# upper_final.net
KiCad netlist of a schematic drawn in EAGLE
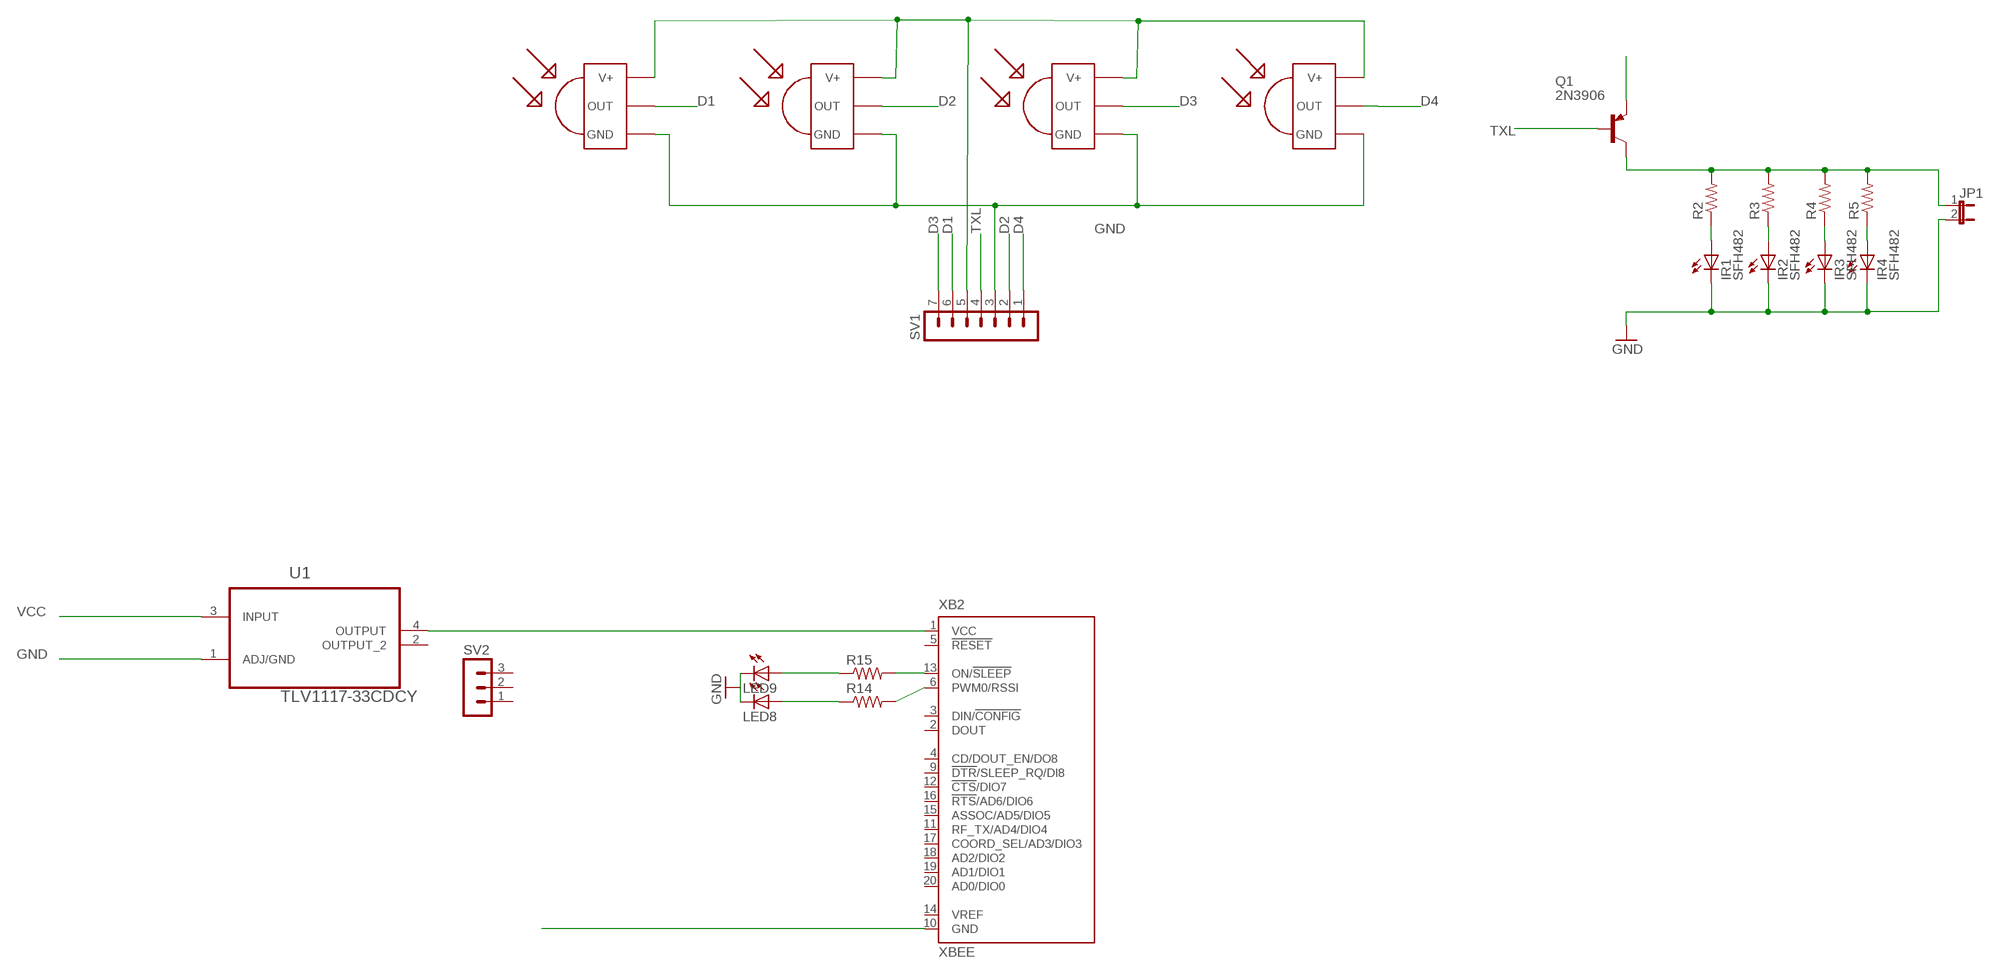
[diagram p0: schematic, sheet 1]

(export (version "E")
  (design (tool "Eeschema 10.0.6"))
  (components
    (comp (ref "IR1")
      (value "SFH482")
      (footprint "eagle-import:SFH482")
      (libsource (lib "eagle-import") (part "SFH482"))
    )
    (comp (ref "IR2")
      (value "SFH482")
      (footprint "eagle-import:SFH482")
      (libsource (lib "eagle-import") (part "SFH482"))
    )
    (comp (ref "IR3")
      (value "SFH482")
      (footprint "eagle-import:SFH482")
      (libsource (lib "eagle-import") (part "SFH482"))
    )
    (comp (ref "IR4")
      (value "SFH482")
      (footprint "eagle-import:SFH482")
      (libsource (lib "eagle-import") (part "SFH482"))
    )
    (comp (ref "JP1")
      (value "JP1E")
      (footprint "eagle-import:JP1")
      (libsource (lib "eagle-import") (part "JP1E"))
    )
    (comp (ref "LED8")
      (value "LED3MM")
      (footprint "eagle-import:LED3MM")
      (libsource (lib "eagle-import") (part "LED3MM"))
    )
    (comp (ref "LED9")
      (value "LED3MM")
      (footprint "eagle-import:LED3MM")
      (libsource (lib "eagle-import") (part "LED3MM"))
    )
    (comp (ref "Q1")
      (value "2N3906")
      (footprint "eagle-import:TO92")
      (libsource (lib "eagle-import") (part "2N3906"))
    )
    (comp (ref "R2")
      (value "R-US_0204/7")
      (footprint "eagle-import:0204_7")
      (libsource (lib "eagle-import") (part "resistor_R-US_0204/7"))
    )
    (comp (ref "R3")
      (value "R-US_0204/7")
      (footprint "eagle-import:0204_7")
      (libsource (lib "eagle-import") (part "resistor_R-US_0204/7"))
    )
    (comp (ref "R4")
      (value "R-US_0204/7")
      (footprint "eagle-import:0204_7")
      (libsource (lib "eagle-import") (part "resistor_R-US_0204/7"))
    )
    (comp (ref "R5")
      (value "R-US_0204/7")
      (footprint "eagle-import:0204_7")
      (libsource (lib "eagle-import") (part "resistor_R-US_0204/7"))
    )
    (comp (ref "R14")
      (value "R-US_0207/10")
      (footprint "eagle-import:0207_10")
      (libsource (lib "eagle-import") (part "R-US_0207/10"))
    )
    (comp (ref "R15")
      (value "R-US_0207/10")
      (footprint "eagle-import:0207_10")
      (libsource (lib "eagle-import") (part "R-US_0207/10"))
    )
    (comp (ref "SV1")
      (value "MA07-1")
      (footprint "eagle-import:MA07-1")
      (libsource (lib "eagle-import") (part "MA07-1"))
    )
    (comp (ref "SV2")
      (value "MA03-1")
      (footprint "eagle-import:MA03-1")
      (libsource (lib "eagle-import") (part "MA03-1"))
    )
    (comp (ref "U$1")
      (value "TSOP1738")
      (footprint "eagle-import:TSOP17XX")
      (libsource (lib "eagle-import") (part "TSOP1738"))
    )
    (comp (ref "U$2")
      (value "TSOP1738")
      (footprint "eagle-import:TSOP17XX")
      (libsource (lib "eagle-import") (part "TSOP1738"))
    )
    (comp (ref "U$3")
      (value "TSOP1738")
      (footprint "eagle-import:TSOP17XX")
      (libsource (lib "eagle-import") (part "TSOP1738"))
    )
    (comp (ref "U$4")
      (value "TSOP1738")
      (footprint "eagle-import:TSOP17XX")
      (libsource (lib "eagle-import") (part "TSOP1738"))
    )
    (comp (ref "U1")
      (value "TLV1117-33CDCY")
      (footprint "eagle-import:SOT230P700X180-4N")
      (libsource (lib "eagle-import") (part "TLV1117-33CDCY"))
    )
    (comp (ref "XB2")
      (value "XBEE")
      (footprint "eagle-import:XBEE")
      (fields (field (name "MPN") "XBP24-Z7UIT-004"))
      (libsource (lib "eagle-import") (part "XBEE"))
    )
  )
  (nets
    (net (code "1") (name "/D1") (class "Default")
      (node (ref "SV1") (pin "6") (pinfunction "6_6") (pintype "passive"))
      (node (ref "U$1") (pin "OUT") (pinfunction "OUT_OUT") (pintype "bidirectional"))
    )
    (net (code "2") (name "/D2") (class "Default")
      (node (ref "SV1") (pin "2") (pinfunction "2_2") (pintype "passive"))
      (node (ref "U$2") (pin "OUT") (pinfunction "OUT_OUT") (pintype "bidirectional"))
    )
    (net (code "3") (name "/D3") (class "Default")
      (node (ref "SV1") (pin "7") (pinfunction "7_7") (pintype "passive"))
      (node (ref "U$3") (pin "OUT") (pinfunction "OUT_OUT") (pintype "bidirectional"))
    )
    (net (code "4") (name "/D4") (class "Default")
      (node (ref "SV1") (pin "1") (pinfunction "1_1") (pintype "passive"))
      (node (ref "U$4") (pin "OUT") (pinfunction "OUT_OUT") (pintype "bidirectional"))
    )
    (net (code "5") (name "/TXL") (class "Default")
      (node (ref "Q1") (pin "2") (pinfunction "B_2") (pintype "passive"))
      (node (ref "SV1") (pin "4") (pinfunction "4_4") (pintype "passive"))
    )
    (net (code "6") (name "/VCC") (class "Default")
      (node (ref "Q1") (pin "3") (pinfunction "E_3") (pintype "passive"))
      (node (ref "SV1") (pin "5") (pinfunction "5_5") (pintype "passive"))
      (node (ref "U$1") (pin "V+") (pinfunction "V+_V+") (pintype "bidirectional"))
      (node (ref "U$2") (pin "V+") (pinfunction "V+_V+") (pintype "bidirectional"))
      (node (ref "U$3") (pin "V+") (pinfunction "V+_V+") (pintype "bidirectional"))
      (node (ref "U$4") (pin "V+") (pinfunction "V+_V+") (pintype "bidirectional"))
      (node (ref "U1") (pin "3") (pinfunction "INPUT_3") (pintype "input"))
    )
    (net (code "7") (name "GND") (class "Default")
      (node (ref "IR1") (pin "K") (pinfunction "C_K") (pintype "passive"))
      (node (ref "IR2") (pin "K") (pinfunction "C_K") (pintype "passive"))
      (node (ref "IR3") (pin "K") (pinfunction "C_K") (pintype "passive"))
      (node (ref "IR4") (pin "K") (pinfunction "C_K") (pintype "passive"))
      (node (ref "JP1") (pin "2") (pinfunction "2_2") (pintype "passive"))
      (node (ref "LED8") (pin "K") (pinfunction "C_K") (pintype "passive"))
      (node (ref "LED9") (pin "K") (pinfunction "C_K") (pintype "passive"))
      (node (ref "SV1") (pin "3") (pinfunction "3_3") (pintype "passive"))
      (node (ref "U$1") (pin "GND") (pinfunction "GND_GND") (pintype "bidirectional"))
      (node (ref "U$2") (pin "GND") (pinfunction "GND_GND") (pintype "bidirectional"))
      (node (ref "U$3") (pin "GND") (pinfunction "GND_GND") (pintype "bidirectional"))
      (node (ref "U$4") (pin "GND") (pinfunction "GND_GND") (pintype "bidirectional"))
      (node (ref "U1") (pin "1") (pinfunction "ADJ/GND_1") (pintype "input"))
      (node (ref "XB2") (pin "10") (pinfunction "GND_10") (pintype "power_in"))
    )
    (net (code "8") (name "Net-(IR1-PadA)") (class "Default")
      (node (ref "IR1") (pin "A") (pinfunction "A_A") (pintype "passive"))
      (node (ref "R2") (pin "1") (pinfunction "1_1") (pintype "passive"))
    )
    (net (code "9") (name "Net-(IR2-PadA)") (class "Default")
      (node (ref "IR2") (pin "A") (pinfunction "A_A") (pintype "passive"))
      (node (ref "R3") (pin "1") (pinfunction "1_1") (pintype "passive"))
    )
    (net (code "10") (name "Net-(IR3-PadA)") (class "Default")
      (node (ref "IR3") (pin "A") (pinfunction "A_A") (pintype "passive"))
      (node (ref "R4") (pin "1") (pinfunction "1_1") (pintype "passive"))
    )
    (net (code "11") (name "Net-(IR4-PadA)") (class "Default")
      (node (ref "IR4") (pin "A") (pinfunction "A_A") (pintype "passive"))
      (node (ref "R5") (pin "1") (pinfunction "1_1") (pintype "passive"))
    )
    (net (code "12") (name "Net-(LED8-PadA)") (class "Default")
      (node (ref "LED8") (pin "A") (pinfunction "A_A") (pintype "passive"))
      (node (ref "R14") (pin "1") (pinfunction "1_1") (pintype "passive"))
    )
    (net (code "13") (name "Net-(LED9-PadA)") (class "Default")
      (node (ref "LED9") (pin "A") (pinfunction "A_A") (pintype "passive"))
      (node (ref "R15") (pin "1") (pinfunction "1_1") (pintype "passive"))
    )
    (net (code "14") (name "Net-(Q1-C)") (class "Default")
      (node (ref "JP1") (pin "1") (pinfunction "1_1") (pintype "passive"))
      (node (ref "Q1") (pin "1") (pinfunction "C_1") (pintype "passive"))
      (node (ref "R2") (pin "2") (pinfunction "2_2") (pintype "passive"))
      (node (ref "R3") (pin "2") (pinfunction "2_2") (pintype "passive"))
      (node (ref "R4") (pin "2") (pinfunction "2_2") (pintype "passive"))
      (node (ref "R5") (pin "2") (pinfunction "2_2") (pintype "passive"))
    )
    (net (code "15") (name "Net-(U1-OUTPUT)") (class "Default")
      (node (ref "U1") (pin "4") (pinfunction "OUTPUT_4") (pintype "output"))
      (node (ref "XB2") (pin "1") (pinfunction "VCC_1") (pintype "power_in"))
    )
    (net (code "16") (name "Net-(XB2-ON{slash}~{SLEEP})") (class "Default")
      (node (ref "R15") (pin "2") (pinfunction "2_2") (pintype "passive"))
      (node (ref "XB2") (pin "13") (pinfunction "ON/~{SLEEP}_13") (pintype "output"))
    )
    (net (code "17") (name "Net-(XB2-PWM0{slash}RSSI)") (class "Default")
      (node (ref "R14") (pin "2") (pinfunction "2_2") (pintype "passive"))
      (node (ref "XB2") (pin "6") (pinfunction "PWM0/RSSI_6") (pintype "output"))
    )
    (net (code "18") (name "unconnected-(SV2-Pad1)") (class "Default")
      (node (ref "SV2") (pin "1") (pinfunction "1_1") (pintype "passive"))
    )
    (net (code "19") (name "unconnected-(SV2-Pad2)") (class "Default")
      (node (ref "SV2") (pin "2") (pinfunction "2_2") (pintype "passive"))
    )
    (net (code "20") (name "unconnected-(SV2-Pad3)") (class "Default")
      (node (ref "SV2") (pin "3") (pinfunction "3_3") (pintype "passive"))
    )
    (net (code "21") (name "unconnected-(U1-OUTPUT_2-Pad2)") (class "Default")
      (node (ref "U1") (pin "2") (pinfunction "OUTPUT_2_2") (pintype "output"))
    )
    (net (code "22") (name "unconnected-(XB2-AD0{slash}DIO0-Pad20)") (class "Default")
      (node (ref "XB2") (pin "20") (pinfunction "AD0/DIO0_20") (pintype "bidirectional"))
    )
    (net (code "23") (name "unconnected-(XB2-AD1{slash}DIO1-Pad19)") (class "Default")
      (node (ref "XB2") (pin "19") (pinfunction "AD1/DIO1_19") (pintype "bidirectional"))
    )
    (net (code "24") (name "unconnected-(XB2-AD2{slash}DIO2-Pad18)") (class "Default")
      (node (ref "XB2") (pin "18") (pinfunction "AD2/DIO2_18") (pintype "bidirectional"))
    )
    (net (code "25") (name "unconnected-(XB2-ASSOC{slash}AD5{slash}DIO5-Pad15)") (class "Default")
      (node (ref "XB2") (pin "15") (pinfunction "ASSOC/AD5/DIO5_15") (pintype "bidirectional"))
    )
    (net (code "26") (name "unconnected-(XB2-CD{slash}DOUT_EN{slash}DO8-Pad4)") (class "Default")
      (node (ref "XB2") (pin "4") (pinfunction "CD/DOUT_EN/DO8_4") (pintype "output"))
    )
    (net (code "27") (name "unconnected-(XB2-COORD_SEL{slash}AD3{slash}DIO3-Pad17)") (class "Default")
      (node (ref "XB2") (pin "17") (pinfunction "COORD_SEL/AD3/DIO3_17") (pintype "bidirectional"))
    )
    (net (code "28") (name "unconnected-(XB2-DIN{slash}~{CONFIG}-Pad3)") (class "Default")
      (node (ref "XB2") (pin "3") (pinfunction "DIN/~{CONFIG}_3") (pintype "input"))
    )
    (net (code "29") (name "unconnected-(XB2-DOUT-Pad2)") (class "Default")
      (node (ref "XB2") (pin "2") (pinfunction "DOUT_2") (pintype "output"))
    )
    (net (code "30") (name "unconnected-(XB2-RF_TX{slash}AD4{slash}DIO4-Pad11)") (class "Default")
      (node (ref "XB2") (pin "11") (pinfunction "RF_TX/AD4/DIO4_11") (pintype "bidirectional"))
    )
    (net (code "31") (name "unconnected-(XB2-VREF-Pad14)") (class "Default")
      (node (ref "XB2") (pin "14") (pinfunction "VREF_14") (pintype "input"))
    )
    (net (code "32") (name "unconnected-(XB2-~{CTS}{slash}DIO7-Pad12)") (class "Default")
      (node (ref "XB2") (pin "12") (pinfunction "~{CTS}/DIO7_12") (pintype "bidirectional"))
    )
    (net (code "33") (name "unconnected-(XB2-~{DTR}{slash}SLEEP_RQ{slash}DI8-Pad9)") (class "Default")
      (node (ref "XB2") (pin "9") (pinfunction "~{DTR}/SLEEP_RQ/DI8_9") (pintype "bidirectional"))
    )
    (net (code "34") (name "unconnected-(XB2-~{RESET}-Pad5)") (class "Default")
      (node (ref "XB2") (pin "5") (pinfunction "~{RESET}_5") (pintype "input"))
    )
    (net (code "35") (name "unconnected-(XB2-~{RTS}{slash}AD6{slash}DIO6-Pad16)") (class "Default")
      (node (ref "XB2") (pin "16") (pinfunction "~{RTS}/AD6/DIO6_16") (pintype "bidirectional"))
    )
  )
)
